# asset-tracker-v008.net
KiCad netlist of a schematic drawn in EAGLE
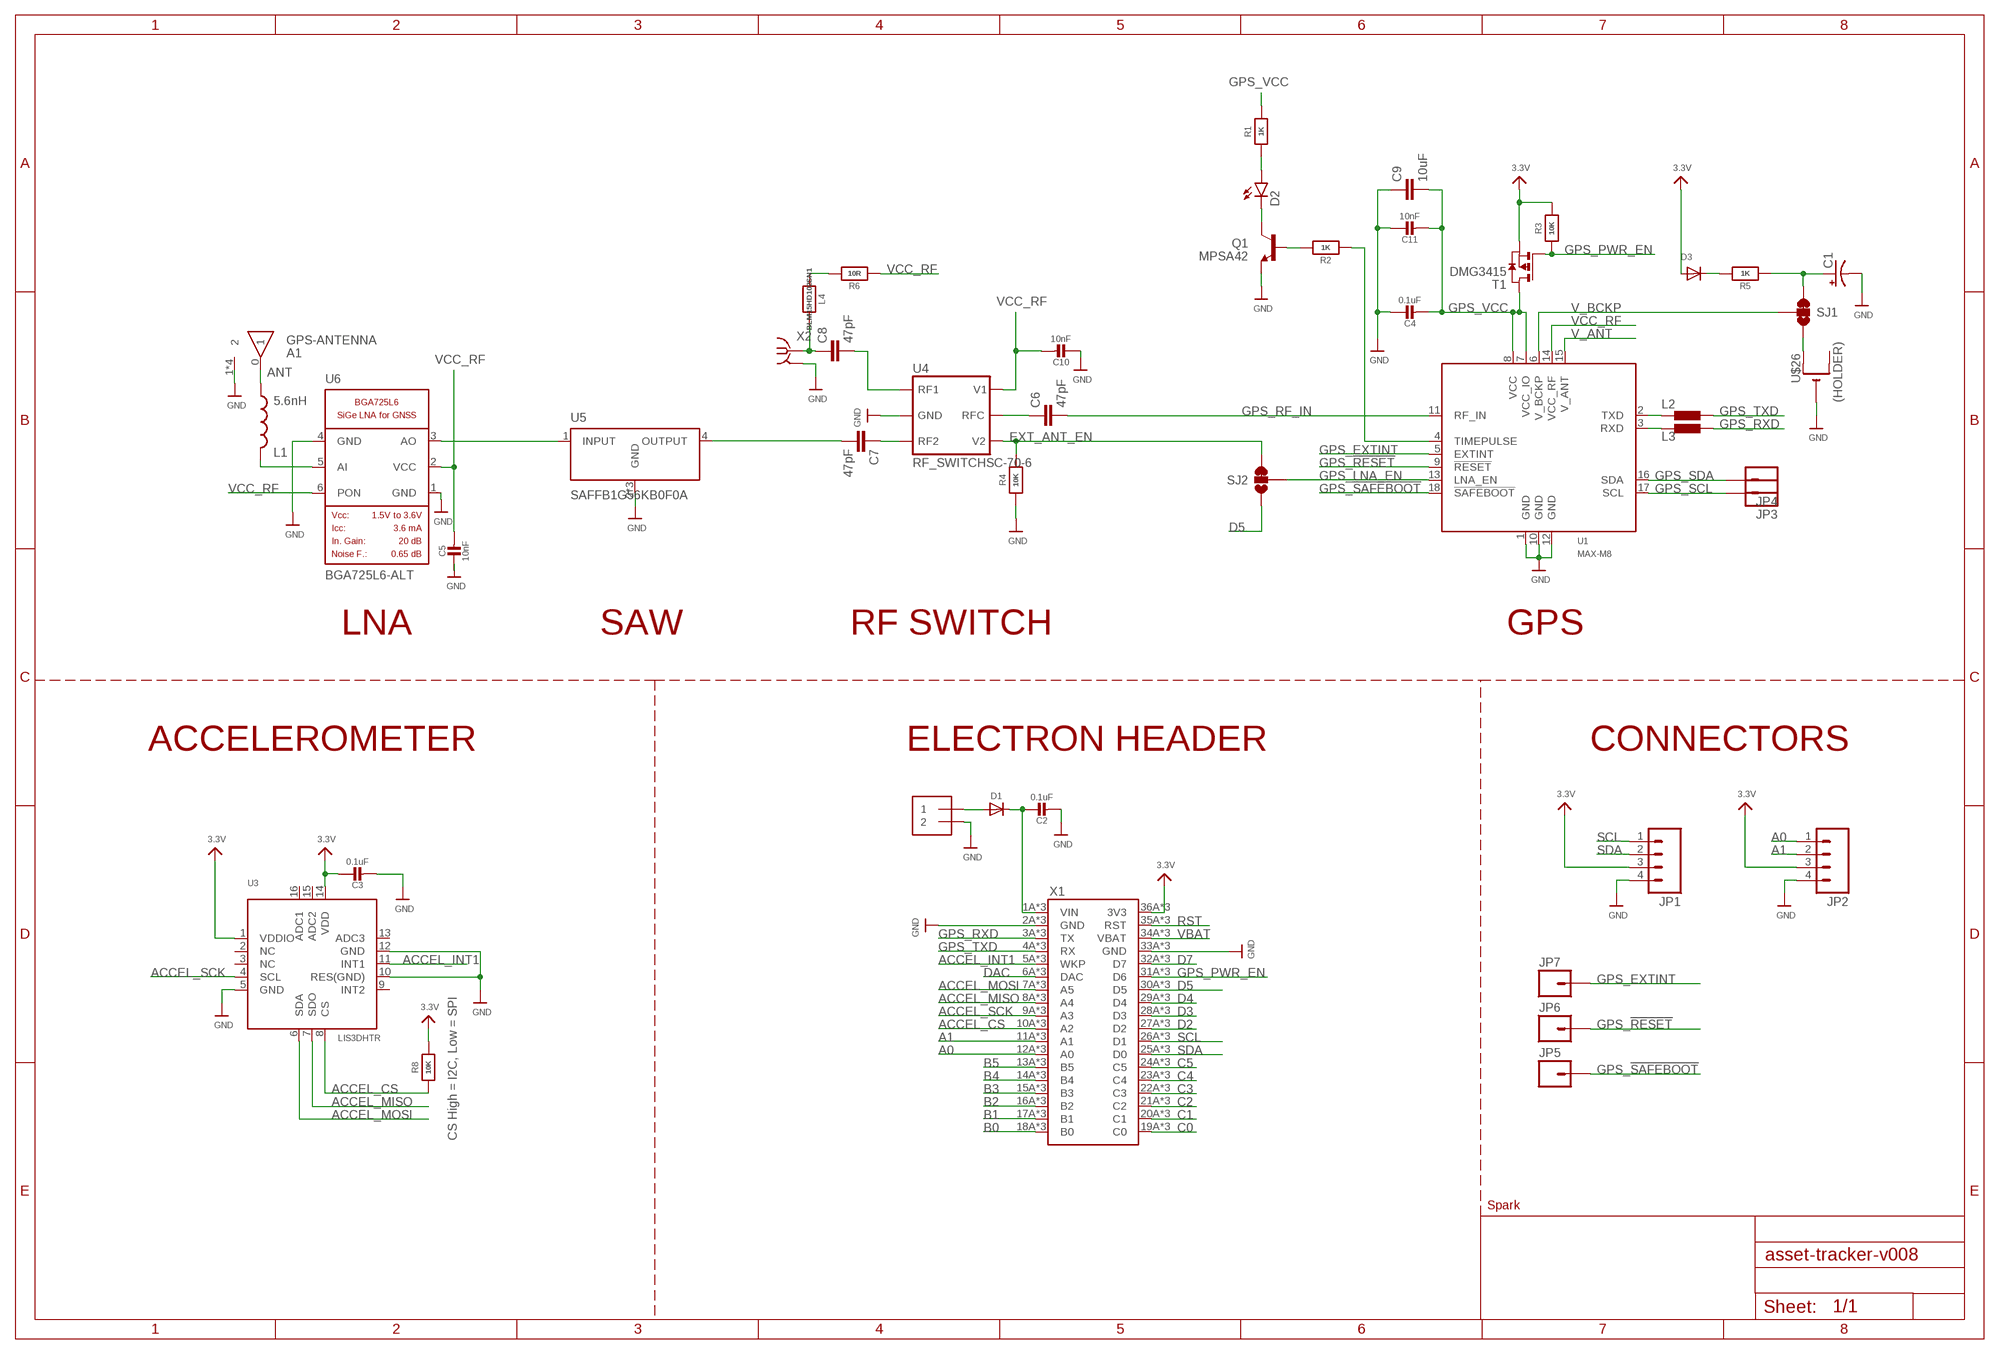
[diagram p0: schematic, sheet 1]

(export (version "E")
  (design (tool "Eeschema 10.0.6"))
  (components
    (comp (ref "A1")
      (value "GPS-ANTENNA")
      (footprint "eagle-import:ANT1818B00BT1516S")
      (libsource (lib "eagle-import") (part "GPS-ANTENNA"))
    )
    (comp (ref "C1")
      (value "SUPERCAP")
      (footprint "eagle-import:414-VA5R")
      (libsource (lib "eagle-import") (part "SUPERCAP"))
    )
    (comp (ref "C2")
      (value "0.1uF")
      (footprint "eagle-import:_0402MP")
      (libsource (lib "eagle-import") (part "microbuilder_CAP_CERAMIC_0402MP"))
    )
    (comp (ref "C3")
      (value "0.1uF")
      (footprint "eagle-import:_0402MP")
      (libsource (lib "eagle-import") (part "microbuilder_CAP_CERAMIC_0402MP"))
    )
    (comp (ref "C4")
      (value "0.1uF")
      (footprint "eagle-import:_0402MP")
      (libsource (lib "eagle-import") (part "CAP_CERAMIC_0402MP"))
    )
    (comp (ref "C5")
      (value "10nF")
      (footprint "eagle-import:_0402MP")
      (libsource (lib "eagle-import") (part "CAP_CERAMIC_0402MP"))
    )
    (comp (ref "C6")
      (value "47pF")
      (footprint "eagle-import:C0201")
      (libsource (lib "eagle-import") (part "C-EUC0201"))
    )
    (comp (ref "C7")
      (value "47pF")
      (footprint "eagle-import:C0201")
      (libsource (lib "eagle-import") (part "C-EUC0201"))
    )
    (comp (ref "C8")
      (value "47pF")
      (footprint "eagle-import:C0201")
      (libsource (lib "eagle-import") (part "C-EUC0201"))
    )
    (comp (ref "C9")
      (value "10uF")
      (footprint "eagle-import:C0402")
      (libsource (lib "eagle-import") (part "C-EUC0402"))
    )
    (comp (ref "C10")
      (value "10nF")
      (footprint "eagle-import:_0402MP")
      (libsource (lib "eagle-import") (part "CAP_CERAMIC_0402MP"))
    )
    (comp (ref "C11")
      (value "10nF")
      (footprint "eagle-import:_0402MP")
      (libsource (lib "eagle-import") (part "CAP_CERAMIC_0402MP"))
    )
    (comp (ref "D1")
      (value "DIODESMA")
      (footprint "eagle-import:SMADIODE")
      (libsource (lib "eagle-import") (part "microbuilder_DIODESMA"))
    )
    (comp (ref "D2")
      (value "LED0603")
      (footprint "eagle-import:LED-0603")
      (libsource (lib "eagle-import") (part "LED0603"))
    )
    (comp (ref "D3")
      (value "DIODESOD-523")
      (footprint "eagle-import:SOD-523")
      (libsource (lib "eagle-import") (part "DIODESOD-523"))
    )
    (comp (ref "J1")
      (value "1X2-3.5MM")
      (footprint "eagle-import:1X2-3.5MM")
      (libsource (lib "eagle-import") (part "1X2-3.5MM"))
    )
    (comp (ref "JP1")
      (value "M04GROVE")
      (footprint "eagle-import:CONNCTOR_GROVE")
      (libsource (lib "eagle-import") (part "M04GROVE"))
    )
    (comp (ref "JP2")
      (value "M04GROVE")
      (footprint "eagle-import:CONNCTOR_GROVE")
      (libsource (lib "eagle-import") (part "M04GROVE"))
    )
    (comp (ref "JP3")
      (value "M01SMD-4.5X1.5")
      (footprint "eagle-import:PAD-1.5X4.5")
      (libsource (lib "eagle-import") (part "M01SMD-4.5X1.5"))
    )
    (comp (ref "JP4")
      (value "M01SMD-4.5X1.5")
      (footprint "eagle-import:PAD-1.5X4.5")
      (libsource (lib "eagle-import") (part "M01SMD-4.5X1.5"))
    )
    (comp (ref "JP5")
      (value "M01SMD-4.5X1.5")
      (footprint "eagle-import:PAD-1.5X4.5")
      (libsource (lib "eagle-import") (part "M01SMD-4.5X1.5"))
    )
    (comp (ref "JP6")
      (value "M01SMD-4.5X1.5")
      (footprint "eagle-import:PAD-1.5X4.5")
      (libsource (lib "eagle-import") (part "M01SMD-4.5X1.5"))
    )
    (comp (ref "JP7")
      (value "M01SMD-4.5X1.5")
      (footprint "eagle-import:PAD-1.5X4.5")
      (libsource (lib "eagle-import") (part "M01SMD-4.5X1.5"))
    )
    (comp (ref "L1")
      (value "5.6nH")
      (footprint "eagle-import:C0402")
      (libsource (lib "eagle-import") (part "INDUCTOR0402"))
    )
    (comp (ref "L2")
      (value "BLM15H2")
      (footprint "eagle-import:_0402MP")
      (libsource (lib "eagle-import") (part "BLM15H2"))
    )
    (comp (ref "L3")
      (value "BLM15H2")
      (footprint "eagle-import:_0402MP")
      (libsource (lib "eagle-import") (part "BLM15H2"))
    )
    (comp (ref "L4")
      (value "BLM15HD102SN1")
      (footprint "eagle-import:_0402MP")
      (libsource (lib "eagle-import") (part "microbuilder_RESISTOR_0402MP"))
    )
    (comp (ref "Q1")
      (value "MPSA42")
      (footprint "eagle-import:SOT23-3")
      (libsource (lib "eagle-import") (part "TRANSISTOR_NPNMPSA42"))
    )
    (comp (ref "R1")
      (value "1K")
      (footprint "eagle-import:_0402MP")
      (libsource (lib "eagle-import") (part "RESISTOR_0402MP"))
    )
    (comp (ref "R2")
      (value "1K")
      (footprint "eagle-import:_0402MP")
      (libsource (lib "eagle-import") (part "RESISTOR_0402MP"))
    )
    (comp (ref "R3")
      (value "10K")
      (footprint "eagle-import:_0402MP")
      (libsource (lib "eagle-import") (part "RESISTOR_0402MP"))
    )
    (comp (ref "R4")
      (value "10K")
      (footprint "eagle-import:_0402MP")
      (libsource (lib "eagle-import") (part "RESISTOR_0402MP"))
    )
    (comp (ref "R5")
      (value "1K")
      (footprint "eagle-import:_0402MP")
      (libsource (lib "eagle-import") (part "RESISTOR_0402MP"))
    )
    (comp (ref "R6")
      (value "10R")
      (footprint "eagle-import:_0402MP")
      (libsource (lib "eagle-import") (part "microbuilder_RESISTOR_0402MP"))
    )
    (comp (ref "R8")
      (value "10K")
      (footprint "eagle-import:_0402MP")
      (libsource (lib "eagle-import") (part "microbuilder_RESISTOR_0402MP"))
    )
    (comp (ref "SJ1")
      (value "JUMPER-PAD-3-2OF3_NC_BY_TRACE_LARGE")
      (footprint "eagle-import:PAD-JUMPER-3-2OF3_NC_BY_TRACE_YES_SILK_LARGE")
      (libsource (lib "eagle-import") (part "JUMPER-PAD-3-2OF3_NC_BY_TRACE_LARGE"))
    )
    (comp (ref "SJ2")
      (value "JUMPER-PAD-3-2OF3_NC_BY_TRACE_LARGE")
      (footprint "eagle-import:PAD-JUMPER-3-2OF3_NC_BY_TRACE_YES_SILK_LARGE")
      (libsource (lib "eagle-import") (part "JUMPER-PAD-3-2OF3_NC_BY_TRACE_LARGE"))
    )
    (comp (ref "T1")
      (value "DMG3415")
      (footprint "eagle-import:SOT-23")
      (libsource (lib "eagle-import") (part "PMOSSOT23"))
    )
    (comp (ref "U$26")
      (value "CR2032SMT")
      (footprint "eagle-import:CR2032-SMD")
      (libsource (lib "eagle-import") (part "CR2032SMT"))
    )
    (comp (ref "U$31")
      (value "SPARK_LOGO")
      (footprint "eagle-import:SPARK_LOGO_TSTOP")
      (libsource (lib "eagle-import") (part "SPARK_LOGO"))
    )
    (comp (ref "U1")
      (value "MAX-M8")
      (footprint "eagle-import:MAX-M8")
      (libsource (lib "eagle-import") (part "MAX-M8"))
    )
    (comp (ref "U3")
      (value "LIS3DHTR")
      (footprint "eagle-import:LGA16_3X3MM")
      (libsource (lib "eagle-import") (part "ACCEL_LIS3DHTR"))
    )
    (comp (ref "U4")
      (value "RF_SWITCHSC-70-6")
      (footprint "eagle-import:SC70-6")
      (libsource (lib "eagle-import") (part "RF_SWITCHSC-70-6"))
    )
    (comp (ref "U5")
      (value "SAFFB1G56KB0F0A")
      (footprint "eagle-import:QCS5I")
      (libsource (lib "eagle-import") (part "FILTERS"))
    )
    (comp (ref "U6")
      (value "BGA725L6-ALT")
      (footprint "eagle-import:LNA-TSLP-6-2-ALT")
      (libsource (lib "eagle-import") (part "BGA725L6-ALT"))
    )
    (comp (ref "X1")
      (value "ELECTRON")
      (footprint "eagle-import:ELECTRON_SMT")
      (libsource (lib "eagle-import") (part "ELECTRON_SMT"))
    )
    (comp (ref "X2")
      (value "IPEX-20279-001E")
      (footprint "eagle-import:IPEX-20279-001E")
      (libsource (lib "eagle-import") (part "IPEX-20279-001E"))
    )
  )
  (nets
    (net (code "1") (name "/A0") (class "Default")
      (node (ref "JP2") (pin "1") (pinfunction "1_1") (pintype "passive"))
      (node (ref "X1") (pin "12A") (pinfunction "A0_12A") (pintype "bidirectional"))
      (node (ref "X1") (pin "12B") (pinfunction "A0_12B") (pintype "bidirectional"))
      (node (ref "X1") (pin "12C") (pinfunction "A0_12C") (pintype "bidirectional"))
    )
    (net (code "2") (name "/A1") (class "Default")
      (node (ref "JP2") (pin "2") (pinfunction "2_2") (pintype "passive"))
      (node (ref "X1") (pin "11A") (pinfunction "A1_11A") (pintype "bidirectional"))
      (node (ref "X1") (pin "11B") (pinfunction "A1_11B") (pintype "bidirectional"))
      (node (ref "X1") (pin "11C") (pinfunction "A1_11C") (pintype "bidirectional"))
    )
    (net (code "3") (name "/ACCEL_CS") (class "Default")
      (node (ref "R8") (pin "1") (pinfunction "1_1") (pintype "passive"))
      (node (ref "U3") (pin "8") (pinfunction "CS_8") (pintype "input"))
      (node (ref "X1") (pin "10A") (pinfunction "A2_10A") (pintype "bidirectional"))
      (node (ref "X1") (pin "10B") (pinfunction "A2_10B") (pintype "bidirectional"))
      (node (ref "X1") (pin "10C") (pinfunction "A2_10C") (pintype "bidirectional"))
    )
    (net (code "4") (name "/ACCEL_INT1") (class "Default")
      (node (ref "U3") (pin "11") (pinfunction "INT1_11") (pintype "output"))
      (node (ref "X1") (pin "5A") (pinfunction "WKP_5A") (pintype "bidirectional"))
      (node (ref "X1") (pin "5B") (pinfunction "WKP_5B") (pintype "bidirectional"))
      (node (ref "X1") (pin "5C") (pinfunction "WKP_5C") (pintype "bidirectional"))
    )
    (net (code "5") (name "/ACCEL_MISO") (class "Default")
      (node (ref "U3") (pin "7") (pinfunction "SDO_7") (pintype "bidirectional"))
      (node (ref "X1") (pin "8A") (pinfunction "A4_8A") (pintype "bidirectional"))
      (node (ref "X1") (pin "8B") (pinfunction "A4_8B") (pintype "bidirectional"))
      (node (ref "X1") (pin "8C") (pinfunction "A4_8C") (pintype "bidirectional"))
    )
    (net (code "6") (name "/ACCEL_MOSI") (class "Default")
      (node (ref "U3") (pin "6") (pinfunction "SDA_6") (pintype "bidirectional"))
      (node (ref "X1") (pin "7A") (pinfunction "A5_7A") (pintype "bidirectional"))
      (node (ref "X1") (pin "7B") (pinfunction "A5_7B") (pintype "bidirectional"))
      (node (ref "X1") (pin "7C") (pinfunction "A5_7C") (pintype "bidirectional"))
    )
    (net (code "7") (name "/ACCEL_SCK") (class "Default")
      (node (ref "U3") (pin "4") (pinfunction "SCL_4") (pintype "bidirectional"))
      (node (ref "X1") (pin "9A") (pinfunction "A3_9A") (pintype "bidirectional"))
      (node (ref "X1") (pin "9B") (pinfunction "A3_9B") (pintype "bidirectional"))
      (node (ref "X1") (pin "9C") (pinfunction "A3_9C") (pintype "bidirectional"))
    )
    (net (code "8") (name "/ANT") (class "Default")
      (node (ref "A1") (pin "0") (pinfunction "1_0") (pintype "output"))
      (node (ref "L1") (pin "2") (pinfunction "2_2") (pintype "passive"))
    )
    (net (code "9") (name "/B0") (class "Default")
      (node (ref "X1") (pin "18A") (pinfunction "B0_18A") (pintype "bidirectional"))
      (node (ref "X1") (pin "18B") (pinfunction "B0_18B") (pintype "bidirectional"))
      (node (ref "X1") (pin "18C") (pinfunction "B0_18C") (pintype "bidirectional"))
    )
    (net (code "10") (name "/B1") (class "Default")
      (node (ref "X1") (pin "17A") (pinfunction "B1_17A") (pintype "bidirectional"))
      (node (ref "X1") (pin "17B") (pinfunction "B1_17B") (pintype "bidirectional"))
      (node (ref "X1") (pin "17C") (pinfunction "B1_17C") (pintype "bidirectional"))
    )
    (net (code "11") (name "/B2") (class "Default")
      (node (ref "X1") (pin "16A") (pinfunction "B2_16A") (pintype "bidirectional"))
      (node (ref "X1") (pin "16B") (pinfunction "B2_16B") (pintype "bidirectional"))
      (node (ref "X1") (pin "16C") (pinfunction "B2_16C") (pintype "bidirectional"))
    )
    (net (code "12") (name "/B3") (class "Default")
      (node (ref "X1") (pin "15A") (pinfunction "B3_15A") (pintype "bidirectional"))
      (node (ref "X1") (pin "15B") (pinfunction "B3_15B") (pintype "bidirectional"))
      (node (ref "X1") (pin "15C") (pinfunction "B3_15C") (pintype "bidirectional"))
    )
    (net (code "13") (name "/B4") (class "Default")
      (node (ref "X1") (pin "14A") (pinfunction "B4_14A") (pintype "bidirectional"))
      (node (ref "X1") (pin "14B") (pinfunction "B4_14B") (pintype "bidirectional"))
      (node (ref "X1") (pin "14C") (pinfunction "B4_14C") (pintype "bidirectional"))
    )
    (net (code "14") (name "/B5") (class "Default")
      (node (ref "X1") (pin "13A") (pinfunction "B5_13A") (pintype "bidirectional"))
      (node (ref "X1") (pin "13B") (pinfunction "B5_13B") (pintype "bidirectional"))
      (node (ref "X1") (pin "13C") (pinfunction "B5_13C") (pintype "bidirectional"))
    )
    (net (code "15") (name "/C0") (class "Default")
      (node (ref "X1") (pin "19A") (pinfunction "C0_19A") (pintype "bidirectional"))
      (node (ref "X1") (pin "19B") (pinfunction "C0_19B") (pintype "bidirectional"))
      (node (ref "X1") (pin "19C") (pinfunction "C0_19C") (pintype "bidirectional"))
    )
    (net (code "16") (name "/C1") (class "Default")
      (node (ref "X1") (pin "20A") (pinfunction "C1_20A") (pintype "bidirectional"))
      (node (ref "X1") (pin "20B") (pinfunction "C1_20B") (pintype "bidirectional"))
      (node (ref "X1") (pin "20C") (pinfunction "C1_20C") (pintype "bidirectional"))
    )
    (net (code "17") (name "/C2") (class "Default")
      (node (ref "X1") (pin "21A") (pinfunction "C2_21A") (pintype "bidirectional"))
      (node (ref "X1") (pin "21B") (pinfunction "C2_21B") (pintype "bidirectional"))
      (node (ref "X1") (pin "21C") (pinfunction "C2_21C") (pintype "bidirectional"))
    )
    (net (code "18") (name "/C3") (class "Default")
      (node (ref "X1") (pin "22A") (pinfunction "C3_22A") (pintype "bidirectional"))
      (node (ref "X1") (pin "22B") (pinfunction "C3_22B") (pintype "bidirectional"))
      (node (ref "X1") (pin "22C") (pinfunction "C3_22C") (pintype "bidirectional"))
    )
    (net (code "19") (name "/C4") (class "Default")
      (node (ref "X1") (pin "23A") (pinfunction "C4_23A") (pintype "bidirectional"))
      (node (ref "X1") (pin "23B") (pinfunction "C4_23B") (pintype "bidirectional"))
      (node (ref "X1") (pin "23C") (pinfunction "C4_23C") (pintype "bidirectional"))
    )
    (net (code "20") (name "/C5") (class "Default")
      (node (ref "X1") (pin "24A") (pinfunction "C5_24A") (pintype "bidirectional"))
      (node (ref "X1") (pin "24B") (pinfunction "C5_24B") (pintype "bidirectional"))
      (node (ref "X1") (pin "24C") (pinfunction "C5_24C") (pintype "bidirectional"))
    )
    (net (code "21") (name "/D2") (class "Default")
      (node (ref "X1") (pin "27A") (pinfunction "D2_27A") (pintype "bidirectional"))
      (node (ref "X1") (pin "27B") (pinfunction "D2_27B") (pintype "bidirectional"))
      (node (ref "X1") (pin "27C") (pinfunction "D2_27C") (pintype "bidirectional"))
    )
    (net (code "22") (name "/D3") (class "Default")
      (node (ref "X1") (pin "28A") (pinfunction "D3_28A") (pintype "bidirectional"))
      (node (ref "X1") (pin "28B") (pinfunction "D3_28B") (pintype "bidirectional"))
      (node (ref "X1") (pin "28C") (pinfunction "D3_28C") (pintype "bidirectional"))
    )
    (net (code "23") (name "/D4") (class "Default")
      (node (ref "X1") (pin "29A") (pinfunction "D4_29A") (pintype "bidirectional"))
      (node (ref "X1") (pin "29B") (pinfunction "D4_29B") (pintype "bidirectional"))
      (node (ref "X1") (pin "29C") (pinfunction "D4_29C") (pintype "bidirectional"))
    )
    (net (code "24") (name "/D5") (class "Default")
      (node (ref "SJ2") (pin "1") (pinfunction "1_1") (pintype "passive"))
      (node (ref "X1") (pin "30A") (pinfunction "D5_30A") (pintype "bidirectional"))
      (node (ref "X1") (pin "30B") (pinfunction "D5_30B") (pintype "bidirectional"))
      (node (ref "X1") (pin "30C") (pinfunction "D5_30C") (pintype "bidirectional"))
    )
    (net (code "25") (name "/D7") (class "Default")
      (node (ref "X1") (pin "32A") (pinfunction "D7_32A") (pintype "bidirectional"))
      (node (ref "X1") (pin "32B") (pinfunction "D7_32B") (pintype "bidirectional"))
      (node (ref "X1") (pin "32C") (pinfunction "D7_32C") (pintype "bidirectional"))
    )
    (net (code "26") (name "/DAC") (class "Default")
      (node (ref "X1") (pin "6A") (pinfunction "DAC_6A") (pintype "bidirectional"))
      (node (ref "X1") (pin "6B") (pinfunction "DAC_6B") (pintype "bidirectional"))
      (node (ref "X1") (pin "6C") (pinfunction "DAC_6C") (pintype "bidirectional"))
    )
    (net (code "27") (name "/EXT_ANT_EN") (class "Default")
      (node (ref "R4") (pin "2") (pinfunction "2_2") (pintype "passive"))
      (node (ref "SJ2") (pin "3") (pinfunction "3_3") (pintype "passive"))
      (node (ref "U4") (pin "4") (pinfunction "V2_4") (pintype "input"))
    )
    (net (code "28") (name "/GPS_EXTINT") (class "Default")
      (node (ref "JP7") (pin "P$1") (pinfunction "1_P$1") (pintype "passive"))
      (node (ref "U1") (pin "5") (pinfunction "EXTINT_5") (pintype "bidirectional"))
    )
    (net (code "29") (name "/GPS_LNA_EN") (class "Default")
      (node (ref "SJ2") (pin "2") (pinfunction "2_2") (pintype "passive"))
      (node (ref "U1") (pin "13") (pinfunction "LNA_EN_13") (pintype "bidirectional"))
    )
    (net (code "30") (name "/GPS_PWR_EN") (class "Default")
      (node (ref "R3") (pin "1") (pinfunction "1_1") (pintype "passive"))
      (node (ref "T1") (pin "3") (pinfunction "G_3") (pintype "passive"))
      (node (ref "X1") (pin "31A") (pinfunction "D6_31A") (pintype "bidirectional"))
      (node (ref "X1") (pin "31B") (pinfunction "D6_31B") (pintype "bidirectional"))
      (node (ref "X1") (pin "31C") (pinfunction "D6_31C") (pintype "bidirectional"))
    )
    (net (code "31") (name "/GPS_RF_IN") (class "Default")
      (node (ref "C6") (pin "2") (pinfunction "2_2") (pintype "passive"))
      (node (ref "U1") (pin "11") (pinfunction "RF_IN_11") (pintype "bidirectional"))
    )
    (net (code "32") (name "/GPS_RXD") (class "Default")
      (node (ref "L3") (pin "2") (pinfunction "2_2") (pintype "passive"))
      (node (ref "X1") (pin "3A") (pinfunction "TX_3A") (pintype "bidirectional"))
      (node (ref "X1") (pin "3B") (pinfunction "TX_3B") (pintype "bidirectional"))
      (node (ref "X1") (pin "3C") (pinfunction "TX_3C") (pintype "bidirectional"))
    )
    (net (code "33") (name "/GPS_SCL") (class "Default")
      (node (ref "JP3") (pin "P$1") (pinfunction "1_P$1") (pintype "passive"))
      (node (ref "U1") (pin "17") (pinfunction "SCL_17") (pintype "bidirectional"))
    )
    (net (code "34") (name "/GPS_SDA") (class "Default")
      (node (ref "JP4") (pin "P$1") (pinfunction "1_P$1") (pintype "passive"))
      (node (ref "U1") (pin "16") (pinfunction "SDA_16") (pintype "bidirectional"))
    )
    (net (code "35") (name "/GPS_TXD") (class "Default")
      (node (ref "L2") (pin "2") (pinfunction "2_2") (pintype "passive"))
      (node (ref "X1") (pin "4A") (pinfunction "RX_4A") (pintype "bidirectional"))
      (node (ref "X1") (pin "4B") (pinfunction "RX_4B") (pintype "bidirectional"))
      (node (ref "X1") (pin "4C") (pinfunction "RX_4C") (pintype "bidirectional"))
    )
    (net (code "36") (name "/GPS_VCC") (class "Default")
      (node (ref "C11") (pin "2") (pinfunction "2_2") (pintype "passive"))
      (node (ref "C4") (pin "2") (pinfunction "2_2") (pintype "passive"))
      (node (ref "C9") (pin "2") (pinfunction "2_2") (pintype "passive"))
      (node (ref "R1") (pin "2") (pinfunction "2_2") (pintype "passive"))
      (node (ref "T1") (pin "1") (pinfunction "D_1") (pintype "passive"))
      (node (ref "U1") (pin "7") (pinfunction "VCC_IO_7") (pintype "bidirectional"))
      (node (ref "U1") (pin "8") (pinfunction "VCC_8") (pintype "bidirectional"))
    )
    (net (code "37") (name "/GPS_~{RESET}") (class "Default")
      (node (ref "JP6") (pin "P$1") (pinfunction "1_P$1") (pintype "passive"))
      (node (ref "U1") (pin "9") (pinfunction "~{RESET}_9") (pintype "bidirectional"))
    )
    (net (code "38") (name "/GPS_~{SAFEBOOT}") (class "Default")
      (node (ref "JP5") (pin "P$1") (pinfunction "1_P$1") (pintype "passive"))
      (node (ref "U1") (pin "18") (pinfunction "~{SAFEBOOT}_18") (pintype "bidirectional"))
    )
    (net (code "39") (name "/RST") (class "Default")
      (node (ref "X1") (pin "35A") (pinfunction "RST_35A") (pintype "bidirectional"))
      (node (ref "X1") (pin "35B") (pinfunction "RST_35B") (pintype "bidirectional"))
      (node (ref "X1") (pin "35C") (pinfunction "RST_35C") (pintype "bidirectional"))
    )
    (net (code "40") (name "/SCL") (class "Default")
      (node (ref "JP1") (pin "1") (pinfunction "1_1") (pintype "passive"))
      (node (ref "X1") (pin "26A") (pinfunction "D1_26A") (pintype "bidirectional"))
      (node (ref "X1") (pin "26B") (pinfunction "D1_26B") (pintype "bidirectional"))
      (node (ref "X1") (pin "26C") (pinfunction "D1_26C") (pintype "bidirectional"))
    )
    (net (code "41") (name "/SDA") (class "Default")
      (node (ref "JP1") (pin "2") (pinfunction "2_2") (pintype "passive"))
      (node (ref "X1") (pin "25A") (pinfunction "D0_25A") (pintype "bidirectional"))
      (node (ref "X1") (pin "25B") (pinfunction "D0_25B") (pintype "bidirectional"))
      (node (ref "X1") (pin "25C") (pinfunction "D0_25C") (pintype "bidirectional"))
    )
    (net (code "42") (name "/VBAT") (class "Default")
      (node (ref "X1") (pin "34A") (pinfunction "VBAT_34A") (pintype "passive"))
      (node (ref "X1") (pin "34B") (pinfunction "VBAT_34B") (pintype "passive"))
      (node (ref "X1") (pin "34C") (pinfunction "VBAT_34C") (pintype "passive"))
    )
    (net (code "43") (name "/VCC_RF") (class "Default")
      (node (ref "C10") (pin "2") (pinfunction "2_2") (pintype "passive"))
      (node (ref "C5") (pin "2") (pinfunction "2_2") (pintype "passive"))
      (node (ref "R6") (pin "1") (pinfunction "1_1") (pintype "passive"))
      (node (ref "U1") (pin "14") (pinfunction "VCC_RF_14") (pintype "bidirectional"))
      (node (ref "U4") (pin "6") (pinfunction "V1_6") (pintype "input"))
      (node (ref "U6") (pin "2") (pinfunction "VCC_2") (pintype "power_in"))
      (node (ref "U6") (pin "6") (pinfunction "PON_6") (pintype "input"))
    )
    (net (code "44") (name "/V_ANT") (class "Default")
      (node (ref "U1") (pin "15") (pinfunction "V_ANT_15") (pintype "bidirectional"))
    )
    (net (code "45") (name "/V_BCKP") (class "Default")
      (node (ref "SJ1") (pin "2") (pinfunction "2_2") (pintype "passive"))
      (node (ref "U1") (pin "6") (pinfunction "V_BCKP_6") (pintype "bidirectional"))
    )
    (net (code "46") (name "3.3V") (class "Default")
      (node (ref "C3") (pin "1") (pinfunction "1_1") (pintype "passive"))
      (node (ref "D3") (pin "A") (pinfunction "A_A") (pintype "passive"))
      (node (ref "JP1") (pin "3") (pinfunction "3_3") (pintype "passive"))
      (node (ref "JP2") (pin "3") (pinfunction "3_3") (pintype "passive"))
      (node (ref "R3") (pin "2") (pinfunction "2_2") (pintype "passive"))
      (node (ref "R8") (pin "2") (pinfunction "2_2") (pintype "passive"))
      (node (ref "T1") (pin "2") (pinfunction "S_2") (pintype "passive"))
      (node (ref "U3") (pin "1") (pinfunction "VDDIO_1") (pintype "power_in"))
      (node (ref "U3") (pin "14") (pinfunction "VDD_14") (pintype "power_in"))
      (node (ref "X1") (pin "36A") (pinfunction "3V3_36A") (pintype "power_in"))
      (node (ref "X1") (pin "36B") (pinfunction "3V3_36B") (pintype "power_in"))
      (node (ref "X1") (pin "36C") (pinfunction "3V3_36C") (pintype "power_in"))
    )
    (net (code "47") (name "GND") (class "Default")
      (node (ref "A1") (pin "1") (pinfunction "2_1") (pintype "power_in"))
      (node (ref "A1") (pin "2") (pinfunction "2_2") (pintype "power_in"))
      (node (ref "A1") (pin "3") (pinfunction "2_3") (pintype "power_in"))
      (node (ref "A1") (pin "4") (pinfunction "2_4") (pintype "power_in"))
      (node (ref "C1") (pin "-") (pinfunction "-_-") (pintype "passive"))
      (node (ref "C10") (pin "1") (pinfunction "1_1") (pintype "passive"))
      (node (ref "C11") (pin "1") (pinfunction "1_1") (pintype "passive"))
      (node (ref "C2") (pin "2") (pinfunction "2_2") (pintype "passive"))
      (node (ref "C3") (pin "2") (pinfunction "2_2") (pintype "passive"))
      (node (ref "C4") (pin "1") (pinfunction "1_1") (pintype "passive"))
      (node (ref "C5") (pin "1") (pinfunction "1_1") (pintype "passive"))
      (node (ref "C9") (pin "1") (pinfunction "1_1") (pintype "passive"))
      (node (ref "J1") (pin "2") (pinfunction "2_2") (pintype "passive"))
      (node (ref "JP1") (pin "4") (pinfunction "4_4") (pintype "passive"))
      (node (ref "JP2") (pin "4") (pinfunction "4_4") (pintype "passive"))
      (node (ref "Q1") (pin "2") (pinfunction "E_2") (pintype "passive"))
      (node (ref "R4") (pin "1") (pinfunction "1_1") (pintype "passive"))
      (node (ref "U$26") (pin "-") (pinfunction "-_-") (pintype "passive"))
      (node (ref "U1") (pin "1") (pinfunction "GND_1") (pintype "bidirectional"))
      (node (ref "U1") (pin "10") (pinfunction "GND_10") (pintype "bidirectional"))
      (node (ref "U1") (pin "12") (pinfunction "GND_12") (pintype "bidirectional"))
      (node (ref "U3") (pin "10") (pinfunction "RES(GND)_10") (pintype "bidirectional"))
      (node (ref "U3") (pin "12") (pinfunction "GND_12") (pintype "power_in"))
      (node (ref "U3") (pin "5") (pinfunction "GND_5") (pintype "power_in"))
      (node (ref "U4") (pin "2") (pinfunction "GND_2") (pintype "power_in"))
      (node (ref "U5") (pin "2") (pinfunction "GND_2") (pintype "power_in"))
      (node (ref "U5") (pin "3") (pinfunction "GND_3") (pintype "power_in"))
      (node (ref "U5") (pin "5") (pinfunction "GND_5") (pintype "power_in"))
      (node (ref "U6") (pin "1") (pinfunction "GND_1") (pintype "power_in"))
      (node (ref "U6") (pin "4") (pinfunction "GND_4") (pintype "power_in"))
      (node (ref "X1") (pin "2A") (pinfunction "GND_2A") (pintype "power_in"))
      (node (ref "X1") (pin "2B") (pinfunction "GND_2B") (pintype "power_in"))
      (node (ref "X1") (pin "2C") (pinfunction "GND_2C") (pintype "power_in"))
      (node (ref "X1") (pin "33A") (pinfunction "GND_33A") (pintype "power_in"))
      (node (ref "X1") (pin "33B") (pinfunction "GND_33B") (pintype "power_in"))
      (node (ref "X1") (pin "33C") (pinfunction "GND_33C") (pintype "power_in"))
      (node (ref "X2") (pin "2@1") (pinfunction "GND_2@1") (pintype "passive"))
      (node (ref "X2") (pin "2@2") (pinfunction "GND_2@2") (pintype "passive"))
    )
    (net (code "48") (name "Net-(C1-Pad+)") (class "Default")
      (node (ref "C1") (pin "+") (pinfunction "+_+") (pintype "passive"))
      (node (ref "R5") (pin "1") (pinfunction "1_1") (pintype "passive"))
      (node (ref "SJ1") (pin "3") (pinfunction "3_3") (pintype "passive"))
    )
    (net (code "49") (name "Net-(C2-Pad1)") (class "Default")
      (node (ref "C2") (pin "1") (pinfunction "1_1") (pintype "passive"))
      (node (ref "D1") (pin "C") (pinfunction "C_C") (pintype "passive"))
      (node (ref "X1") (pin "1A") (pinfunction "VIN_1A") (pintype "power_in"))
      (node (ref "X1") (pin "1B") (pinfunction "VIN_1B") (pintype "power_in"))
      (node (ref "X1") (pin "1C") (pinfunction "VIN_1C") (pintype "power_in"))
    )
    (net (code "50") (name "Net-(C8-Pad1)") (class "Default")
      (node (ref "C8") (pin "1") (pinfunction "1_1") (pintype "passive"))
      (node (ref "L4") (pin "2") (pinfunction "2_2") (pintype "passive"))
      (node (ref "X2") (pin "1") (pinfunction "1_1") (pintype "passive"))
    )
    (net (code "51") (name "Net-(D1-PadA)") (class "Default")
      (node (ref "D1") (pin "A") (pinfunction "A_A") (pintype "passive"))
      (node (ref "J1") (pin "1") (pinfunction "1_1") (pintype "passive"))
    )
    (net (code "52") (name "Net-(D2-PadA)") (class "Default")
      (node (ref "D2") (pin "A") (pinfunction "A_A") (pintype "passive"))
      (node (ref "R1") (pin "1") (pinfunction "1_1") (pintype "passive"))
    )
    (net (code "53") (name "Net-(D3-C)") (class "Default")
      (node (ref "D3") (pin "K") (pinfunction "C_K") (pintype "passive"))
      (node (ref "R5") (pin "2") (pinfunction "2_2") (pintype "passive"))
    )
    (net (code "54") (name "Net-(L4-Pad1)") (class "Default")
      (node (ref "L4") (pin "1") (pinfunction "1_1") (pintype "passive"))
      (node (ref "R6") (pin "2") (pinfunction "2_2") (pintype "passive"))
    )
    (net (code "55") (name "Net-(Q1-B)") (class "Default")
      (node (ref "Q1") (pin "1") (pinfunction "B_1") (pintype "passive"))
      (node (ref "R2") (pin "2") (pinfunction "2_2") (pintype "passive"))
    )
    (net (code "56") (name "Net-(Q1-C)") (class "Default")
      (node (ref "D2") (pin "C") (pinfunction "C_C") (pintype "passive"))
      (node (ref "Q1") (pin "3") (pinfunction "C_3") (pintype "passive"))
    )
    (net (code "57") (name "Net-(U$26-+)") (class "Default")
      (node (ref "SJ1") (pin "1") (pinfunction "1_1") (pintype "passive"))
      (node (ref "U$26") (pin "+$1") (pinfunction "+_+$1") (pintype "passive"))
    )
    (net (code "58") (name "Net-(U1-RXD)") (class "Default")
      (node (ref "L3") (pin "1") (pinfunction "1_1") (pintype "passive"))
      (node (ref "U1") (pin "3") (pinfunction "RXD_3") (pintype "bidirectional"))
    )
    (net (code "59") (name "Net-(U1-TIMEPULSE)") (class "Default")
      (node (ref "R2") (pin "1") (pinfunction "1_1") (pintype "passive"))
      (node (ref "U1") (pin "4") (pinfunction "TIMEPULSE_4") (pintype "bidirectional"))
    )
    (net (code "60") (name "Net-(U1-TXD)") (class "Default")
      (node (ref "L2") (pin "1") (pinfunction "1_1") (pintype "passive"))
      (node (ref "U1") (pin "2") (pinfunction "TXD_2") (pintype "bidirectional"))
    )
    (net (code "61") (name "Net-(U4-RF1)") (class "Default")
      (node (ref "C8") (pin "2") (pinfunction "2_2") (pintype "passive"))
      (node (ref "U4") (pin "1") (pinfunction "RF1_1") (pintype "output"))
    )
    (net (code "62") (name "Net-(U4-RF2)") (class "Default")
      (node (ref "C7") (pin "1") (pinfunction "1_1") (pintype "passive"))
      (node (ref "U4") (pin "3") (pinfunction "RF2_3") (pintype "output"))
    )
    (net (code "63") (name "Net-(U4-RFC)") (class "Default")
      (node (ref "C6") (pin "1") (pinfunction "1_1") (pintype "passive"))
      (node (ref "U4") (pin "5") (pinfunction "RFC_5") (pintype "input"))
    )
    (net (code "64") (name "Net-(U5-INPUT)") (class "Default")
      (node (ref "U5") (pin "1") (pinfunction "INPUT_1") (pintype "input"))
      (node (ref "U6") (pin "3") (pinfunction "AO_3") (pintype "output"))
    )
    (net (code "65") (name "Net-(U5-OUTPUT)") (class "Default")
      (node (ref "C7") (pin "2") (pinfunction "2_2") (pintype "passive"))
      (node (ref "U5") (pin "4") (pinfunction "OUTPUT_4") (pintype "bidirectional"))
    )
    (net (code "66") (name "Net-(U6-AI)") (class "Default")
      (node (ref "L1") (pin "1") (pinfunction "1_1") (pintype "passive"))
      (node (ref "U6") (pin "5") (pinfunction "AI_5") (pintype "input"))
    )
    (net (code "67") (name "unconnected-(U$26-+1-Pad+$2)") (class "Default")
      (node (ref "U$26") (pin "+$2") (pinfunction "+1_+$2") (pintype "passive"))
    )
    (net (code "68") (name "unconnected-(U3-ADC1-Pad16)") (class "Default")
      (node (ref "U3") (pin "16") (pinfunction "ADC1_16") (pintype "input"))
    )
    (net (code "69") (name "unconnected-(U3-ADC2-Pad15)") (class "Default")
      (node (ref "U3") (pin "15") (pinfunction "ADC2_15") (pintype "input"))
    )
    (net (code "70") (name "unconnected-(U3-ADC3-Pad13)") (class "Default")
      (node (ref "U3") (pin "13") (pinfunction "ADC3_13") (pintype "input"))
    )
    (net (code "71") (name "unconnected-(U3-INT2-Pad9)") (class "Default")
      (node (ref "U3") (pin "9") (pinfunction "INT2_9") (pintype "output"))
    )
    (net (code "72") (name "unconnected-(U3-NC-Pad2)") (class "Default")
      (node (ref "U3") (pin "2") (pinfunction "NC_2") (pintype "no_connect"))
    )
    (net (code "73") (name "unconnected-(U3-NC-Pad3)") (class "Default")
      (node (ref "U3") (pin "3") (pinfunction "NC_3") (pintype "no_connect"))
    )
  )
)
